# Lock-In_D2.net
KiCad netlist of a schematic drawn in EAGLE
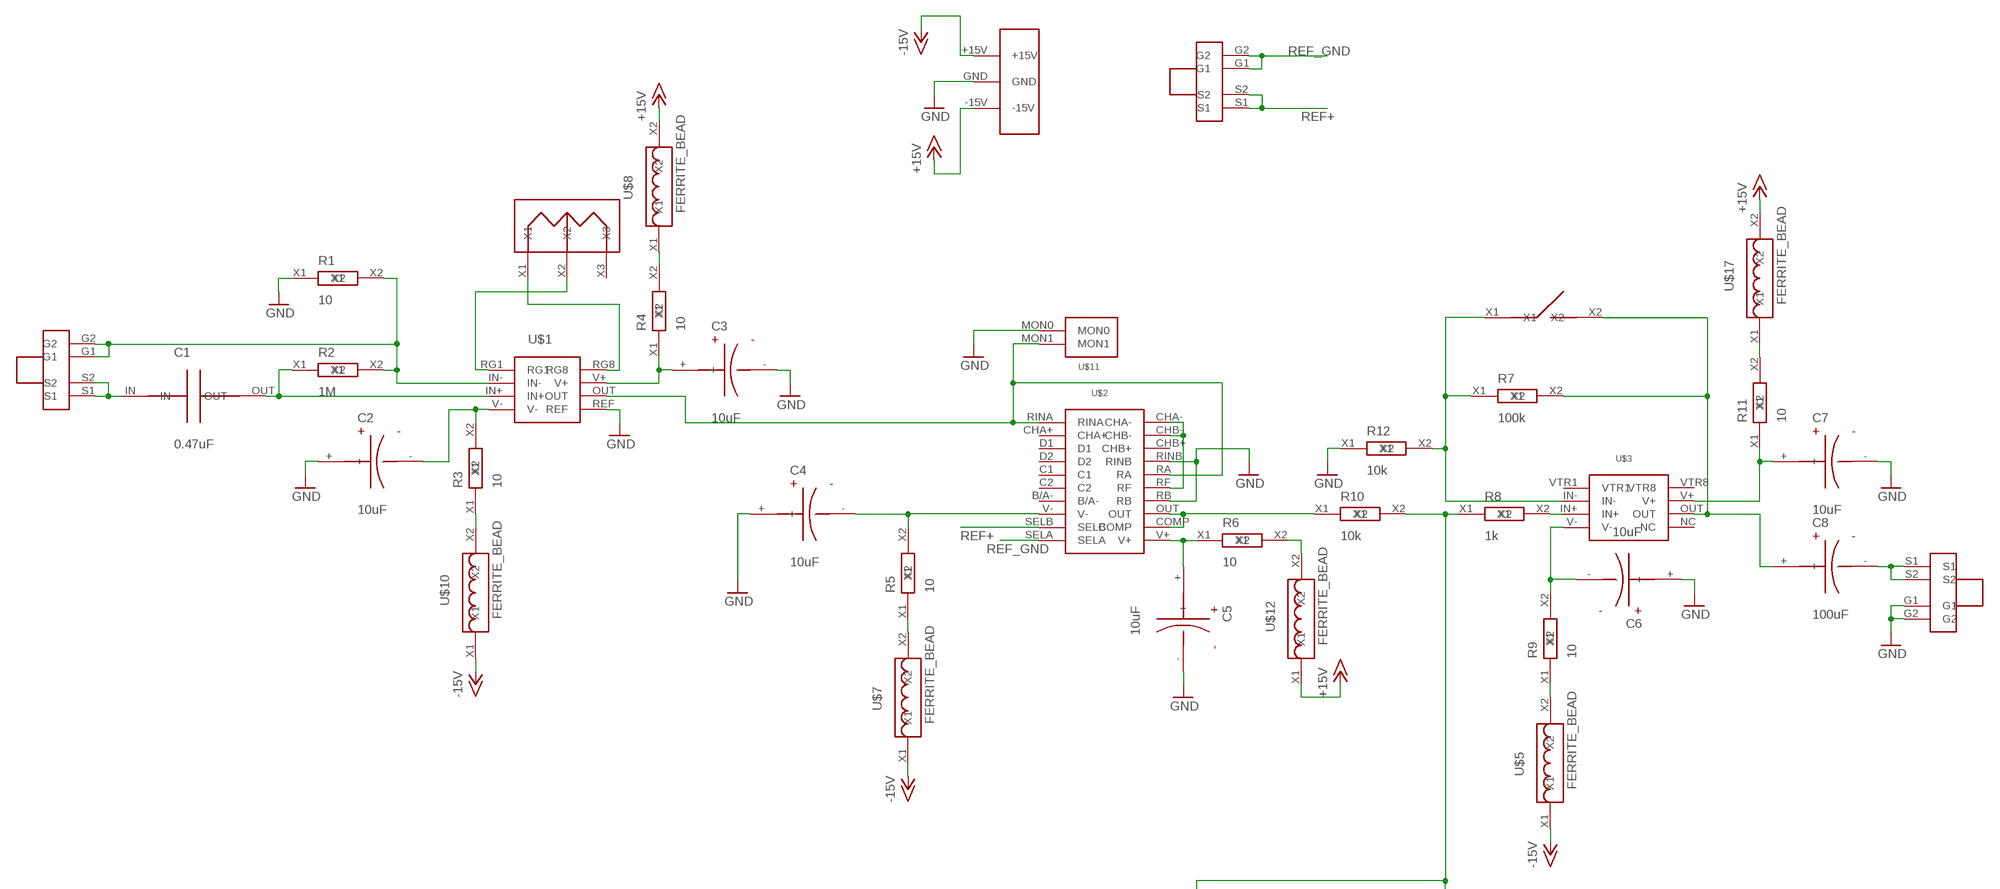
[diagram p0: schematic, sheet 1, part 1 of 2]
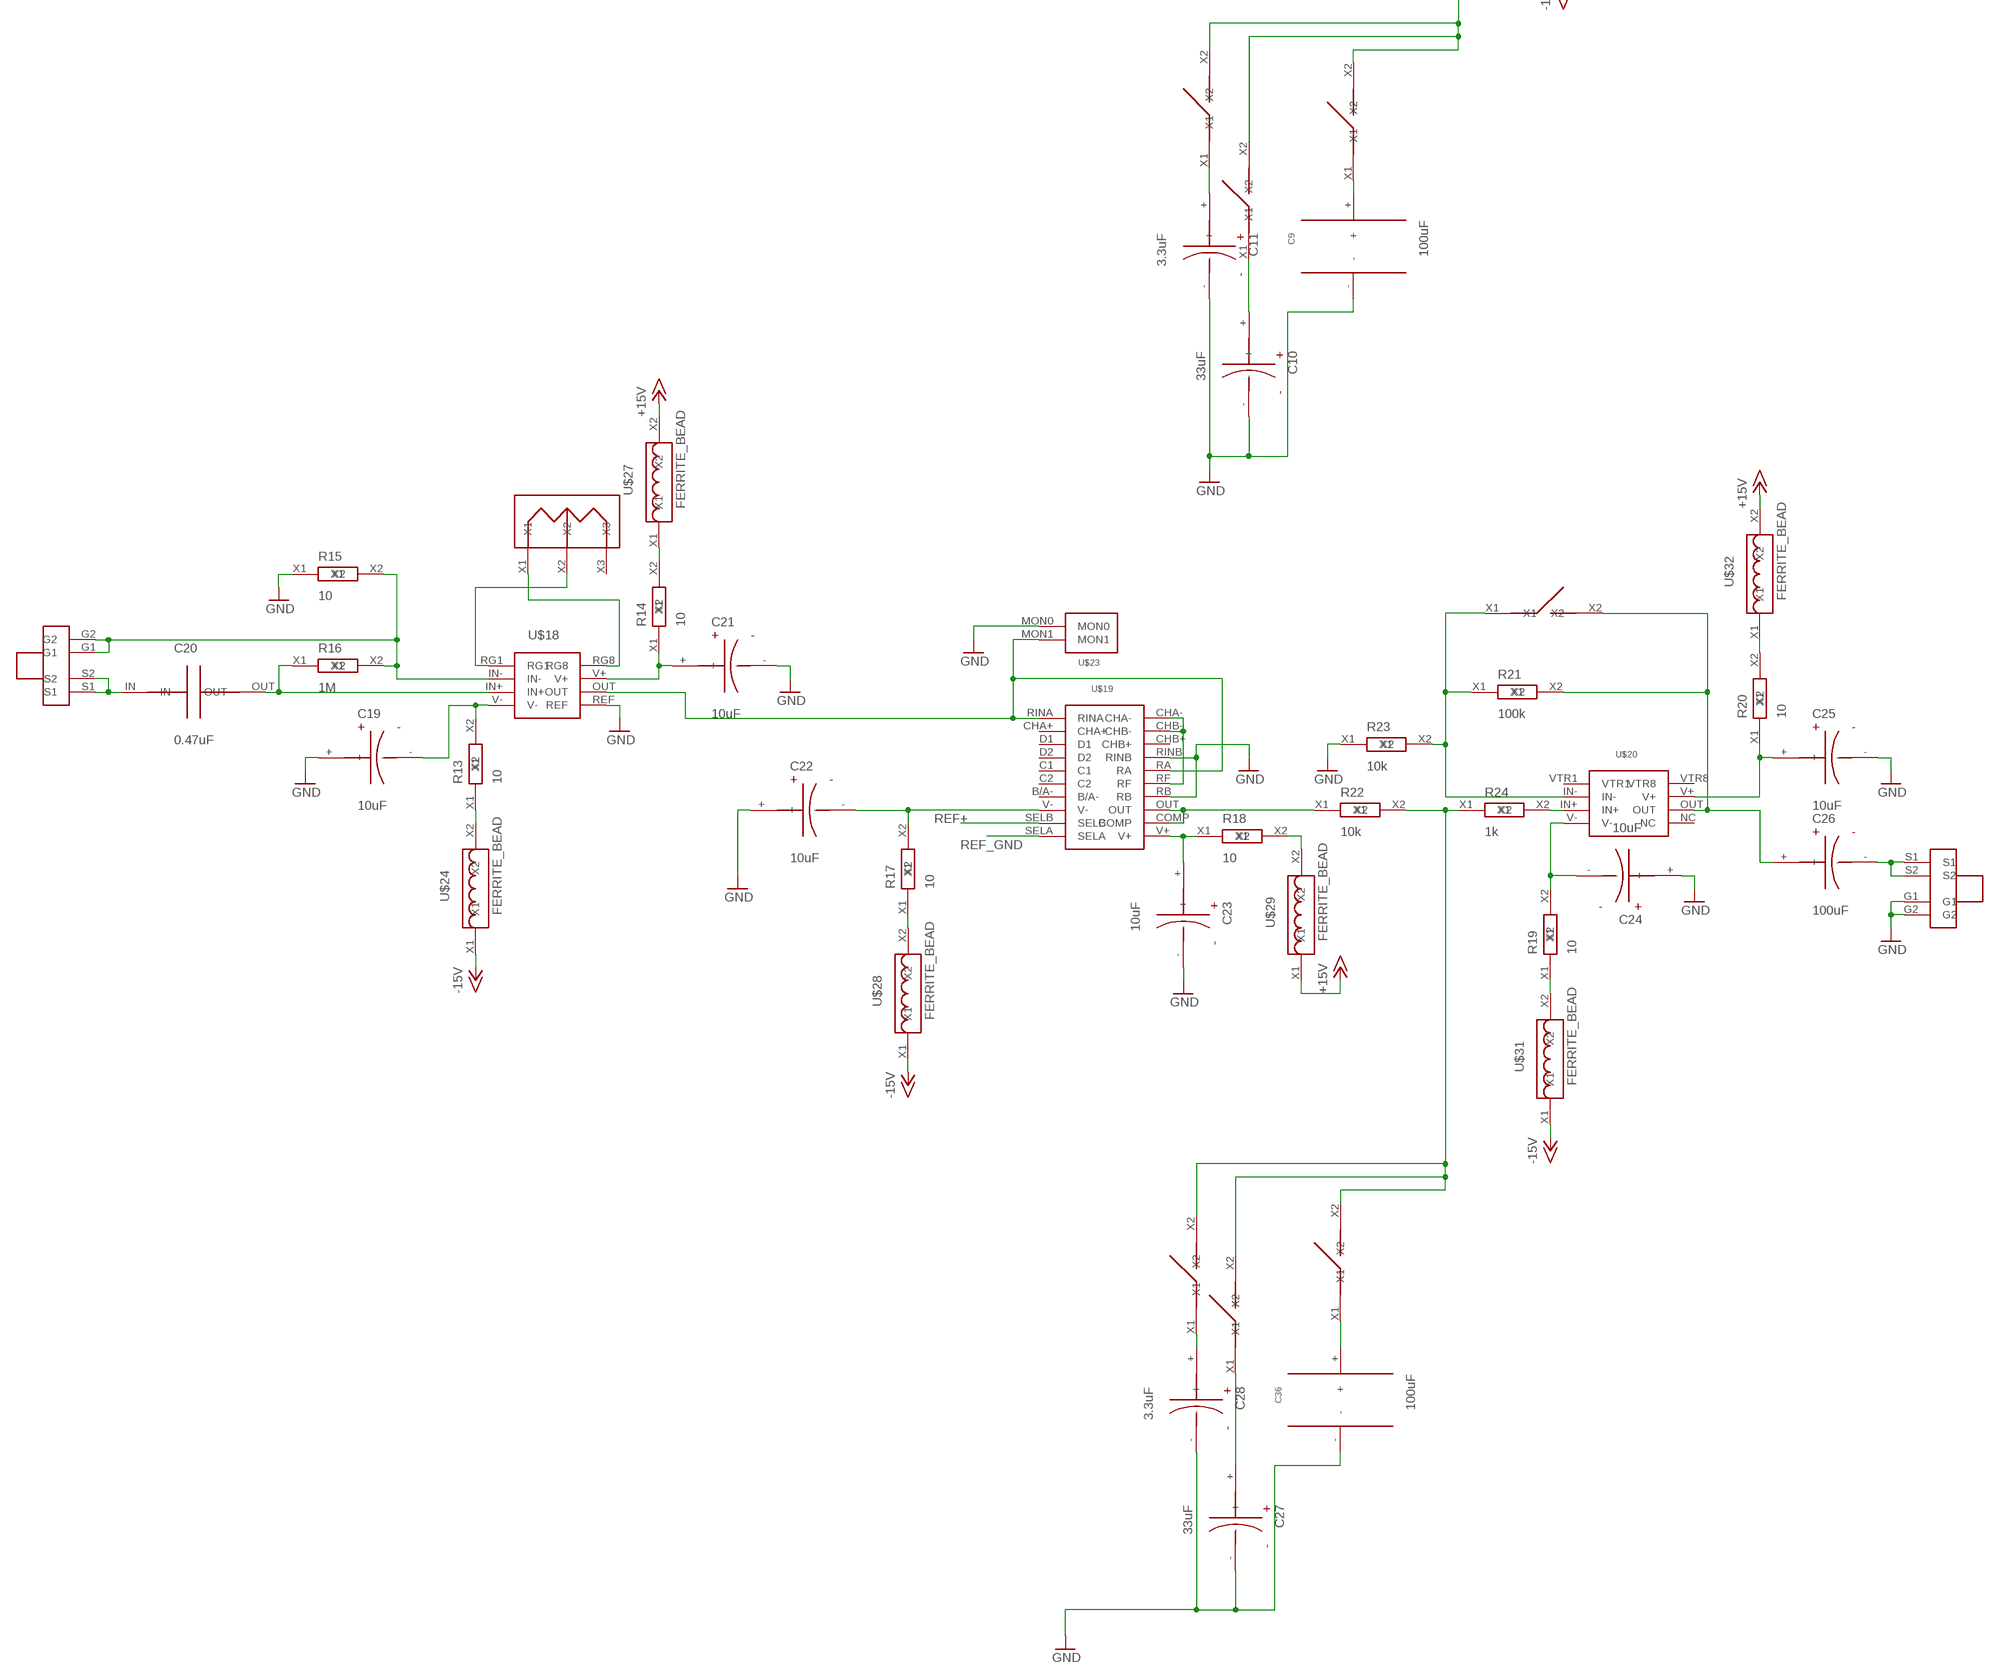
[diagram p1: schematic, sheet 1, part 2 of 2]

(export (version "E")
  (design (tool "Eeschema 10.0.6"))
  (components
    (comp (ref "C1")
      (value "0.47uF")
      (footprint "eagle-import:C_CER_5MM")
      (libsource (lib "eagle-import") (part "C_CER_5MM"))
    )
    (comp (ref "C2")
      (value "10uF")
      (footprint "eagle-import:C_ELT_2MM")
      (libsource (lib "eagle-import") (part "C_ELT_2MM"))
    )
    (comp (ref "C3")
      (value "10uF")
      (footprint "eagle-import:C_ELT_2MM")
      (libsource (lib "eagle-import") (part "C_ELT_2MM"))
    )
    (comp (ref "C4")
      (value "10uF")
      (footprint "eagle-import:C_ELT_2MM")
      (libsource (lib "eagle-import") (part "C_ELT_2MM"))
    )
    (comp (ref "C5")
      (value "10uF")
      (footprint "eagle-import:C_ELT_2MM")
      (libsource (lib "eagle-import") (part "C_ELT_2MM"))
    )
    (comp (ref "C6")
      (value "10uF")
      (footprint "eagle-import:C_ELT_2MM")
      (libsource (lib "eagle-import") (part "C_ELT_2MM"))
    )
    (comp (ref "C7")
      (value "10uF")
      (footprint "eagle-import:C_ELT_2MM")
      (libsource (lib "eagle-import") (part "C_ELT_2MM"))
    )
    (comp (ref "C8")
      (value "100uF")
      (footprint "eagle-import:C_ELT_2MM")
      (libsource (lib "eagle-import") (part "C_ELT_2MM"))
    )
    (comp (ref "C9")
      (value "100uF")
      (footprint "eagle-import:C100UF")
      (libsource (lib "eagle-import") (part "C100UF"))
    )
    (comp (ref "C10")
      (value "33uF")
      (footprint "eagle-import:C_ELT_2MM")
      (libsource (lib "eagle-import") (part "C_ELT_2MM"))
    )
    (comp (ref "C11")
      (value "3.3uF")
      (footprint "eagle-import:C_ELT_2MM")
      (libsource (lib "eagle-import") (part "C_ELT_2MM"))
    )
    (comp (ref "C19")
      (value "10uF")
      (footprint "eagle-import:C_ELT_2MM")
      (libsource (lib "eagle-import") (part "C_ELT_2MM"))
    )
    (comp (ref "C20")
      (value "0.47uF")
      (footprint "eagle-import:C_CER_5MM")
      (libsource (lib "eagle-import") (part "C_CER_5MM"))
    )
    (comp (ref "C21")
      (value "10uF")
      (footprint "eagle-import:C_ELT_2MM")
      (libsource (lib "eagle-import") (part "C_ELT_2MM"))
    )
    (comp (ref "C22")
      (value "10uF")
      (footprint "eagle-import:C_ELT_2MM")
      (libsource (lib "eagle-import") (part "C_ELT_2MM"))
    )
    (comp (ref "C23")
      (value "10uF")
      (footprint "eagle-import:C_ELT_2MM")
      (libsource (lib "eagle-import") (part "C_ELT_2MM"))
    )
    (comp (ref "C24")
      (value "10uF")
      (footprint "eagle-import:C_ELT_2MM")
      (libsource (lib "eagle-import") (part "C_ELT_2MM"))
    )
    (comp (ref "C25")
      (value "10uF")
      (footprint "eagle-import:C_ELT_2MM")
      (libsource (lib "eagle-import") (part "C_ELT_2MM"))
    )
    (comp (ref "C26")
      (value "100uF")
      (footprint "eagle-import:C_ELT_2MM")
      (libsource (lib "eagle-import") (part "C_ELT_2MM"))
    )
    (comp (ref "C27")
      (value "33uF")
      (footprint "eagle-import:C_ELT_2MM")
      (libsource (lib "eagle-import") (part "C_ELT_2MM"))
    )
    (comp (ref "C28")
      (value "3.3uF")
      (footprint "eagle-import:C_ELT_2MM")
      (libsource (lib "eagle-import") (part "C_ELT_2MM"))
    )
    (comp (ref "C36")
      (value "100uF")
      (footprint "eagle-import:C100UF")
      (libsource (lib "eagle-import") (part "C100UF"))
    )
    (comp (ref "R1")
      (value "10")
      (footprint "eagle-import:SMD_2.1X1.25")
      (libsource (lib "eagle-import") (part "R_SMD_2.1X1.25"))
    )
    (comp (ref "R2")
      (value "1M")
      (footprint "eagle-import:SMD_2.1X1.25")
      (libsource (lib "eagle-import") (part "R_SMD_2.1X1.25"))
    )
    (comp (ref "R3")
      (value "10")
      (footprint "eagle-import:SMD_2.1X1.25")
      (libsource (lib "eagle-import") (part "R_SMD_2.1X1.25"))
    )
    (comp (ref "R4")
      (value "10")
      (footprint "eagle-import:SMD_2.1X1.25")
      (libsource (lib "eagle-import") (part "R_SMD_2.1X1.25"))
    )
    (comp (ref "R5")
      (value "10")
      (footprint "eagle-import:SMD_2.1X1.25")
      (libsource (lib "eagle-import") (part "R_SMD_2.1X1.25"))
    )
    (comp (ref "R6")
      (value "10")
      (footprint "eagle-import:SMD_2.1X1.25")
      (libsource (lib "eagle-import") (part "R_SMD_2.1X1.25"))
    )
    (comp (ref "R7")
      (value "100k")
      (footprint "eagle-import:SMD_2.1X1.25")
      (libsource (lib "eagle-import") (part "R_SMD_2.1X1.25"))
    )
    (comp (ref "R8")
      (value "1k")
      (footprint "eagle-import:SMD_2.1X1.25")
      (libsource (lib "eagle-import") (part "R_SMD_2.1X1.25"))
    )
    (comp (ref "R9")
      (value "10")
      (footprint "eagle-import:SMD_2.1X1.25")
      (libsource (lib "eagle-import") (part "R_SMD_2.1X1.25"))
    )
    (comp (ref "R10")
      (value "10k")
      (footprint "eagle-import:SMD_2.1X1.25")
      (libsource (lib "eagle-import") (part "R_SMD_2.1X1.25"))
    )
    (comp (ref "R11")
      (value "10")
      (footprint "eagle-import:SMD_2.1X1.25")
      (libsource (lib "eagle-import") (part "R_SMD_2.1X1.25"))
    )
    (comp (ref "R12")
      (value "10k")
      (footprint "eagle-import:SMD_2.1X1.25")
      (libsource (lib "eagle-import") (part "R_SMD_2.1X1.25"))
    )
    (comp (ref "R13")
      (value "10")
      (footprint "eagle-import:SMD_2.1X1.25")
      (libsource (lib "eagle-import") (part "R_SMD_2.1X1.25"))
    )
    (comp (ref "R14")
      (value "10")
      (footprint "eagle-import:SMD_2.1X1.25")
      (libsource (lib "eagle-import") (part "R_SMD_2.1X1.25"))
    )
    (comp (ref "R15")
      (value "10")
      (footprint "eagle-import:SMD_2.1X1.25")
      (libsource (lib "eagle-import") (part "R_SMD_2.1X1.25"))
    )
    (comp (ref "R16")
      (value "1M")
      (footprint "eagle-import:SMD_2.1X1.25")
      (libsource (lib "eagle-import") (part "R_SMD_2.1X1.25"))
    )
    (comp (ref "R17")
      (value "10")
      (footprint "eagle-import:SMD_2.1X1.25")
      (libsource (lib "eagle-import") (part "R_SMD_2.1X1.25"))
    )
    (comp (ref "R18")
      (value "10")
      (footprint "eagle-import:SMD_2.1X1.25")
      (libsource (lib "eagle-import") (part "R_SMD_2.1X1.25"))
    )
    (comp (ref "R19")
      (value "10")
      (footprint "eagle-import:SMD_2.1X1.25")
      (libsource (lib "eagle-import") (part "R_SMD_2.1X1.25"))
    )
    (comp (ref "R20")
      (value "10")
      (footprint "eagle-import:SMD_2.1X1.25")
      (libsource (lib "eagle-import") (part "R_SMD_2.1X1.25"))
    )
    (comp (ref "R21")
      (value "100k")
      (footprint "eagle-import:SMD_2.1X1.25")
      (libsource (lib "eagle-import") (part "R_SMD_2.1X1.25"))
    )
    (comp (ref "R22")
      (value "10k")
      (footprint "eagle-import:SMD_2.1X1.25")
      (libsource (lib "eagle-import") (part "R_SMD_2.1X1.25"))
    )
    (comp (ref "R23")
      (value "10k")
      (footprint "eagle-import:SMD_2.1X1.25")
      (libsource (lib "eagle-import") (part "R_SMD_2.1X1.25"))
    )
    (comp (ref "R24")
      (value "1k")
      (footprint "eagle-import:SMD_2.1X1.25")
      (libsource (lib "eagle-import") (part "R_SMD_2.1X1.25"))
    )
    (comp (ref "U$1")
      (value "AD620N")
      (footprint "eagle-import:AD620N")
      (libsource (lib "eagle-import") (part "AD620N"))
    )
    (comp (ref "U$2")
      (value "AD630")
      (footprint "eagle-import:AD630")
      (libsource (lib "eagle-import") (part "AD630"))
    )
    (comp (ref "U$3")
      (value "OP27")
      (footprint "eagle-import:OP27")
      (libsource (lib "eagle-import") (part "OP27"))
    )
    (comp (ref "U$4")
      (value "BNC_A")
      (footprint "eagle-import:BNC_A")
      (libsource (lib "eagle-import") (part "BNC_A"))
    )
    (comp (ref "U$5")
      (value "FERRITE_BEAD")
      (footprint "eagle-import:FERRITE_BEAD")
      (libsource (lib "eagle-import") (part "FERRITE_BEAD"))
    )
    (comp (ref "U$6")
      (value "DIP_1")
      (footprint "eagle-import:DIP_1")
      (libsource (lib "eagle-import") (part "DIP_1"))
    )
    (comp (ref "U$7")
      (value "FERRITE_BEAD")
      (footprint "eagle-import:FERRITE_BEAD")
      (libsource (lib "eagle-import") (part "FERRITE_BEAD"))
    )
    (comp (ref "U$8")
      (value "FERRITE_BEAD")
      (footprint "eagle-import:FERRITE_BEAD")
      (libsource (lib "eagle-import") (part "FERRITE_BEAD"))
    )
    (comp (ref "U$9")
      (value "DIP_1")
      (footprint "eagle-import:DIP_1")
      (libsource (lib "eagle-import") (part "DIP_1"))
    )
    (comp (ref "U$10")
      (value "FERRITE_BEAD")
      (footprint "eagle-import:FERRITE_BEAD")
      (libsource (lib "eagle-import") (part "FERRITE_BEAD"))
    )
    (comp (ref "U$11")
      (value "MON2PIN")
      (footprint "eagle-import:MON2PIN")
      (libsource (lib "eagle-import") (part "MON2PIN"))
    )
    (comp (ref "U$12")
      (value "FERRITE_BEAD")
      (footprint "eagle-import:FERRITE_BEAD")
      (libsource (lib "eagle-import") (part "FERRITE_BEAD"))
    )
    (comp (ref "U$13")
      (value "BNC_A")
      (footprint "eagle-import:BNC_A")
      (libsource (lib "eagle-import") (part "BNC_A"))
    )
    (comp (ref "U$14")
      (value "R_VAR_3296W-1-103LF")
      (footprint "eagle-import:R_VAR_3296W-1-103LF")
      (libsource (lib "eagle-import") (part "R_VAR_3296W-1-103LF"))
    )
    (comp (ref "U$15")
      (value "SUPPLY")
      (footprint "eagle-import:SUPPLY")
      (libsource (lib "eagle-import") (part "SUPPLY"))
    )
    (comp (ref "U$16")
      (value "BNC_A")
      (footprint "eagle-import:BNC_A")
      (libsource (lib "eagle-import") (part "BNC_A"))
    )
    (comp (ref "U$17")
      (value "FERRITE_BEAD")
      (footprint "eagle-import:FERRITE_BEAD")
      (libsource (lib "eagle-import") (part "FERRITE_BEAD"))
    )
    (comp (ref "U$18")
      (value "AD620N")
      (footprint "eagle-import:AD620N")
      (libsource (lib "eagle-import") (part "AD620N"))
    )
    (comp (ref "U$19")
      (value "AD630")
      (footprint "eagle-import:AD630")
      (libsource (lib "eagle-import") (part "AD630"))
    )
    (comp (ref "U$20")
      (value "OP27")
      (footprint "eagle-import:OP27")
      (libsource (lib "eagle-import") (part "OP27"))
    )
    (comp (ref "U$21")
      (value "DIP_1")
      (footprint "eagle-import:DIP_1")
      (libsource (lib "eagle-import") (part "DIP_1"))
    )
    (comp (ref "U$22")
      (value "DIP_1")
      (footprint "eagle-import:DIP_1")
      (libsource (lib "eagle-import") (part "DIP_1"))
    )
    (comp (ref "U$23")
      (value "MON2PIN")
      (footprint "eagle-import:MON2PIN")
      (libsource (lib "eagle-import") (part "MON2PIN"))
    )
    (comp (ref "U$24")
      (value "FERRITE_BEAD")
      (footprint "eagle-import:FERRITE_BEAD")
      (libsource (lib "eagle-import") (part "FERRITE_BEAD"))
    )
    (comp (ref "U$25")
      (value "R_VAR_3296W-1-103LF")
      (footprint "eagle-import:R_VAR_3296W-1-103LF")
      (libsource (lib "eagle-import") (part "R_VAR_3296W-1-103LF"))
    )
    (comp (ref "U$26")
      (value "BNC_A")
      (footprint "eagle-import:BNC_A")
      (libsource (lib "eagle-import") (part "BNC_A"))
    )
    (comp (ref "U$27")
      (value "FERRITE_BEAD")
      (footprint "eagle-import:FERRITE_BEAD")
      (libsource (lib "eagle-import") (part "FERRITE_BEAD"))
    )
    (comp (ref "U$28")
      (value "FERRITE_BEAD")
      (footprint "eagle-import:FERRITE_BEAD")
      (libsource (lib "eagle-import") (part "FERRITE_BEAD"))
    )
    (comp (ref "U$29")
      (value "FERRITE_BEAD")
      (footprint "eagle-import:FERRITE_BEAD")
      (libsource (lib "eagle-import") (part "FERRITE_BEAD"))
    )
    (comp (ref "U$30")
      (value "BNC_A")
      (footprint "eagle-import:BNC_A")
      (libsource (lib "eagle-import") (part "BNC_A"))
    )
    (comp (ref "U$31")
      (value "FERRITE_BEAD")
      (footprint "eagle-import:FERRITE_BEAD")
      (libsource (lib "eagle-import") (part "FERRITE_BEAD"))
    )
    (comp (ref "U$32")
      (value "FERRITE_BEAD")
      (footprint "eagle-import:FERRITE_BEAD")
      (libsource (lib "eagle-import") (part "FERRITE_BEAD"))
    )
    (comp (ref "U$33")
      (value "DIP_1")
      (footprint "eagle-import:DIP_1")
      (libsource (lib "eagle-import") (part "DIP_1"))
    )
    (comp (ref "U$34")
      (value "DIP_1")
      (footprint "eagle-import:DIP_1")
      (libsource (lib "eagle-import") (part "DIP_1"))
    )
    (comp (ref "U$35")
      (value "DIP_1")
      (footprint "eagle-import:DIP_1")
      (libsource (lib "eagle-import") (part "DIP_1"))
    )
    (comp (ref "U$36")
      (value "DIP_1")
      (footprint "eagle-import:DIP_1")
      (libsource (lib "eagle-import") (part "DIP_1"))
    )
  )
  (nets
    (net (code "1") (name "+15V") (class "Default")
      (node (ref "U$12") (pin "X1") (pinfunction "X1_X1") (pintype "bidirectional"))
      (node (ref "U$15") (pin "-15V") (pinfunction "-15V_-15V") (pintype "bidirectional"))
      (node (ref "U$17") (pin "X2") (pinfunction "X2_X2") (pintype "bidirectional"))
      (node (ref "U$27") (pin "X2") (pinfunction "X2_X2") (pintype "bidirectional"))
      (node (ref "U$29") (pin "X1") (pinfunction "X1_X1") (pintype "bidirectional"))
      (node (ref "U$32") (pin "X2") (pinfunction "X2_X2") (pintype "bidirectional"))
      (node (ref "U$8") (pin "X2") (pinfunction "X2_X2") (pintype "bidirectional"))
    )
    (net (code "2") (name "-15V") (class "Default")
      (node (ref "U$10") (pin "X1") (pinfunction "X1_X1") (pintype "bidirectional"))
      (node (ref "U$15") (pin "+15V") (pinfunction "+15V_+15V") (pintype "bidirectional"))
      (node (ref "U$24") (pin "X1") (pinfunction "X1_X1") (pintype "bidirectional"))
      (node (ref "U$28") (pin "X1") (pinfunction "X1_X1") (pintype "bidirectional"))
      (node (ref "U$31") (pin "X1") (pinfunction "X1_X1") (pintype "bidirectional"))
      (node (ref "U$5") (pin "X1") (pinfunction "X1_X1") (pintype "bidirectional"))
      (node (ref "U$7") (pin "X1") (pinfunction "X1_X1") (pintype "bidirectional"))
    )
    (net (code "3") (name "/REF+") (class "Default")
      (node (ref "U$13") (pin "S1") (pinfunction "S1_S1") (pintype "bidirectional"))
      (node (ref "U$13") (pin "S2") (pinfunction "S2_S2") (pintype "bidirectional"))
      (node (ref "U$19") (pin "SELB") (pinfunction "SELB_SELB") (pintype "bidirectional"))
      (node (ref "U$2") (pin "SELB") (pinfunction "SELB_SELB") (pintype "bidirectional"))
    )
    (net (code "4") (name "/REF_GND") (class "Default")
      (node (ref "U$13") (pin "G1") (pinfunction "G1_G1") (pintype "bidirectional"))
      (node (ref "U$13") (pin "G2") (pinfunction "G2_G2") (pintype "bidirectional"))
      (node (ref "U$19") (pin "SELA") (pinfunction "SELA_SELA") (pintype "bidirectional"))
      (node (ref "U$2") (pin "SELA") (pinfunction "SELA_SELA") (pintype "bidirectional"))
    )
    (net (code "5") (name "GND") (class "Default")
      (node (ref "C10") (pin "-") (pinfunction "-_-") (pintype "bidirectional"))
      (node (ref "C11") (pin "-") (pinfunction "-_-") (pintype "bidirectional"))
      (node (ref "C19") (pin "+") (pinfunction "+_+") (pintype "bidirectional"))
      (node (ref "C2") (pin "+") (pinfunction "+_+") (pintype "bidirectional"))
      (node (ref "C21") (pin "-") (pinfunction "-_-") (pintype "bidirectional"))
      (node (ref "C22") (pin "+") (pinfunction "+_+") (pintype "bidirectional"))
      (node (ref "C23") (pin "-") (pinfunction "-_-") (pintype "bidirectional"))
      (node (ref "C24") (pin "+") (pinfunction "+_+") (pintype "bidirectional"))
      (node (ref "C25") (pin "-") (pinfunction "-_-") (pintype "bidirectional"))
      (node (ref "C27") (pin "-") (pinfunction "-_-") (pintype "bidirectional"))
      (node (ref "C28") (pin "-") (pinfunction "-_-") (pintype "bidirectional"))
      (node (ref "C3") (pin "-") (pinfunction "-_-") (pintype "bidirectional"))
      (node (ref "C36") (pin "-") (pinfunction "-_-") (pintype "bidirectional"))
      (node (ref "C4") (pin "+") (pinfunction "+_+") (pintype "bidirectional"))
      (node (ref "C5") (pin "-") (pinfunction "-_-") (pintype "bidirectional"))
      (node (ref "C6") (pin "+") (pinfunction "+_+") (pintype "bidirectional"))
      (node (ref "C7") (pin "-") (pinfunction "-_-") (pintype "bidirectional"))
      (node (ref "C9") (pin "-") (pinfunction "-_-") (pintype "bidirectional"))
      (node (ref "R1") (pin "X1") (pinfunction "X1_X1") (pintype "bidirectional"))
      (node (ref "R12") (pin "X1") (pinfunction "X1_X1") (pintype "bidirectional"))
      (node (ref "R15") (pin "X1") (pinfunction "X1_X1") (pintype "bidirectional"))
      (node (ref "R23") (pin "X1") (pinfunction "X1_X1") (pintype "bidirectional"))
      (node (ref "U$1") (pin "REF") (pinfunction "REF_REF") (pintype "bidirectional"))
      (node (ref "U$11") (pin "MON0") (pinfunction "MON0_MON0") (pintype "bidirectional"))
      (node (ref "U$15") (pin "GND") (pinfunction "GND_GND") (pintype "bidirectional"))
      (node (ref "U$18") (pin "REF") (pinfunction "REF_REF") (pintype "bidirectional"))
      (node (ref "U$19") (pin "RB") (pinfunction "RB_RB") (pintype "bidirectional"))
      (node (ref "U$19") (pin "RINB") (pinfunction "RINB_RINB") (pintype "bidirectional"))
      (node (ref "U$2") (pin "RB") (pinfunction "RB_RB") (pintype "bidirectional"))
      (node (ref "U$2") (pin "RINB") (pinfunction "RINB_RINB") (pintype "bidirectional"))
      (node (ref "U$23") (pin "MON0") (pinfunction "MON0_MON0") (pintype "bidirectional"))
      (node (ref "U$30") (pin "G1") (pinfunction "G1_G1") (pintype "bidirectional"))
      (node (ref "U$30") (pin "G2") (pinfunction "G2_G2") (pintype "bidirectional"))
      (node (ref "U$4") (pin "G1") (pinfunction "G1_G1") (pintype "bidirectional"))
      (node (ref "U$4") (pin "G2") (pinfunction "G2_G2") (pintype "bidirectional"))
    )
    (net (code "6") (name "Net-(C1-PadIN)") (class "Default")
      (node (ref "C1") (pin "IN") (pinfunction "IN_IN") (pintype "bidirectional"))
      (node (ref "U$16") (pin "S1") (pinfunction "S1_S1") (pintype "bidirectional"))
      (node (ref "U$16") (pin "S2") (pinfunction "S2_S2") (pintype "bidirectional"))
    )
    (net (code "7") (name "Net-(C1-PadOUT)") (class "Default")
      (node (ref "C1") (pin "OUT") (pinfunction "OUT_OUT") (pintype "bidirectional"))
      (node (ref "R2") (pin "X1") (pinfunction "X1_X1") (pintype "bidirectional"))
      (node (ref "U$1") (pin "IN+") (pinfunction "IN+_IN+") (pintype "bidirectional"))
    )
    (net (code "8") (name "Net-(C2-Pad-)") (class "Default")
      (node (ref "C2") (pin "-") (pinfunction "-_-") (pintype "bidirectional"))
      (node (ref "R3") (pin "X2") (pinfunction "X2_X2") (pintype "bidirectional"))
      (node (ref "U$1") (pin "V-") (pinfunction "V-_V-") (pintype "bidirectional"))
    )
    (net (code "9") (name "Net-(C3-Pad+)") (class "Default")
      (node (ref "C3") (pin "+") (pinfunction "+_+") (pintype "bidirectional"))
      (node (ref "R4") (pin "X1") (pinfunction "X1_X1") (pintype "bidirectional"))
      (node (ref "U$1") (pin "V+") (pinfunction "V+_V+") (pintype "bidirectional"))
    )
    (net (code "10") (name "Net-(C4-Pad-)") (class "Default")
      (node (ref "C4") (pin "-") (pinfunction "-_-") (pintype "bidirectional"))
      (node (ref "R5") (pin "X2") (pinfunction "X2_X2") (pintype "bidirectional"))
      (node (ref "U$2") (pin "V-") (pinfunction "V-_V-") (pintype "bidirectional"))
    )
    (net (code "11") (name "Net-(C5-Pad+)") (class "Default")
      (node (ref "C5") (pin "+") (pinfunction "+_+") (pintype "bidirectional"))
      (node (ref "R6") (pin "X1") (pinfunction "X1_X1") (pintype "bidirectional"))
      (node (ref "U$2") (pin "V+") (pinfunction "V+_V+") (pintype "bidirectional"))
    )
    (net (code "12") (name "Net-(C6-Pad-)") (class "Default")
      (node (ref "C6") (pin "-") (pinfunction "-_-") (pintype "bidirectional"))
      (node (ref "R9") (pin "X2") (pinfunction "X2_X2") (pintype "bidirectional"))
      (node (ref "U$3") (pin "V-") (pinfunction "V-_V-") (pintype "bidirectional"))
    )
    (net (code "13") (name "Net-(C7-Pad+)") (class "Default")
      (node (ref "C7") (pin "+") (pinfunction "+_+") (pintype "bidirectional"))
      (node (ref "R11") (pin "X1") (pinfunction "X1_X1") (pintype "bidirectional"))
      (node (ref "U$3") (pin "V+") (pinfunction "V+_V+") (pintype "bidirectional"))
    )
    (net (code "14") (name "Net-(C8-Pad+)") (class "Default")
      (node (ref "C8") (pin "+") (pinfunction "+_+") (pintype "bidirectional"))
      (node (ref "R7") (pin "X2") (pinfunction "X2_X2") (pintype "bidirectional"))
      (node (ref "U$3") (pin "OUT") (pinfunction "OUT_OUT") (pintype "bidirectional"))
      (node (ref "U$9") (pin "X2") (pinfunction "X2_X2") (pintype "bidirectional"))
    )
    (net (code "15") (name "Net-(C8-Pad-)") (class "Default")
      (node (ref "C8") (pin "-") (pinfunction "-_-") (pintype "bidirectional"))
      (node (ref "U$4") (pin "S1") (pinfunction "S1_S1") (pintype "bidirectional"))
      (node (ref "U$4") (pin "S2") (pinfunction "S2_S2") (pintype "bidirectional"))
    )
    (net (code "16") (name "Net-(C9-Pad+)") (class "Default")
      (node (ref "C9") (pin "+") (pinfunction "+_+") (pintype "bidirectional"))
      (node (ref "U$36") (pin "X1") (pinfunction "X1_X1") (pintype "bidirectional"))
    )
    (net (code "17") (name "Net-(C10-Pad+)") (class "Default")
      (node (ref "C10") (pin "+") (pinfunction "+_+") (pintype "bidirectional"))
      (node (ref "U$35") (pin "X1") (pinfunction "X1_X1") (pintype "bidirectional"))
    )
    (net (code "18") (name "Net-(C11-Pad+)") (class "Default")
      (node (ref "C11") (pin "+") (pinfunction "+_+") (pintype "bidirectional"))
      (node (ref "U$34") (pin "X1") (pinfunction "X1_X1") (pintype "bidirectional"))
    )
    (net (code "19") (name "Net-(C19-Pad-)") (class "Default")
      (node (ref "C19") (pin "-") (pinfunction "-_-") (pintype "bidirectional"))
      (node (ref "R13") (pin "X2") (pinfunction "X2_X2") (pintype "bidirectional"))
      (node (ref "U$18") (pin "V-") (pinfunction "V-_V-") (pintype "bidirectional"))
    )
    (net (code "20") (name "Net-(C20-PadIN)") (class "Default")
      (node (ref "C20") (pin "IN") (pinfunction "IN_IN") (pintype "bidirectional"))
      (node (ref "U$26") (pin "S1") (pinfunction "S1_S1") (pintype "bidirectional"))
      (node (ref "U$26") (pin "S2") (pinfunction "S2_S2") (pintype "bidirectional"))
    )
    (net (code "21") (name "Net-(C20-PadOUT)") (class "Default")
      (node (ref "C20") (pin "OUT") (pinfunction "OUT_OUT") (pintype "bidirectional"))
      (node (ref "R16") (pin "X1") (pinfunction "X1_X1") (pintype "bidirectional"))
      (node (ref "U$18") (pin "IN+") (pinfunction "IN+_IN+") (pintype "bidirectional"))
    )
    (net (code "22") (name "Net-(C21-Pad+)") (class "Default")
      (node (ref "C21") (pin "+") (pinfunction "+_+") (pintype "bidirectional"))
      (node (ref "R14") (pin "X1") (pinfunction "X1_X1") (pintype "bidirectional"))
      (node (ref "U$18") (pin "V+") (pinfunction "V+_V+") (pintype "bidirectional"))
    )
    (net (code "23") (name "Net-(C22-Pad-)") (class "Default")
      (node (ref "C22") (pin "-") (pinfunction "-_-") (pintype "bidirectional"))
      (node (ref "R17") (pin "X2") (pinfunction "X2_X2") (pintype "bidirectional"))
      (node (ref "U$19") (pin "V-") (pinfunction "V-_V-") (pintype "bidirectional"))
    )
    (net (code "24") (name "Net-(C23-Pad+)") (class "Default")
      (node (ref "C23") (pin "+") (pinfunction "+_+") (pintype "bidirectional"))
      (node (ref "R18") (pin "X1") (pinfunction "X1_X1") (pintype "bidirectional"))
      (node (ref "U$19") (pin "V+") (pinfunction "V+_V+") (pintype "bidirectional"))
    )
    (net (code "25") (name "Net-(C24-Pad-)") (class "Default")
      (node (ref "C24") (pin "-") (pinfunction "-_-") (pintype "bidirectional"))
      (node (ref "R19") (pin "X2") (pinfunction "X2_X2") (pintype "bidirectional"))
      (node (ref "U$20") (pin "V-") (pinfunction "V-_V-") (pintype "bidirectional"))
    )
    (net (code "26") (name "Net-(C25-Pad+)") (class "Default")
      (node (ref "C25") (pin "+") (pinfunction "+_+") (pintype "bidirectional"))
      (node (ref "R20") (pin "X1") (pinfunction "X1_X1") (pintype "bidirectional"))
      (node (ref "U$20") (pin "V+") (pinfunction "V+_V+") (pintype "bidirectional"))
    )
    (net (code "27") (name "Net-(C26-Pad+)") (class "Default")
      (node (ref "C26") (pin "+") (pinfunction "+_+") (pintype "bidirectional"))
      (node (ref "R21") (pin "X2") (pinfunction "X2_X2") (pintype "bidirectional"))
      (node (ref "U$20") (pin "OUT") (pinfunction "OUT_OUT") (pintype "bidirectional"))
      (node (ref "U$22") (pin "X2") (pinfunction "X2_X2") (pintype "bidirectional"))
    )
    (net (code "28") (name "Net-(C26-Pad-)") (class "Default")
      (node (ref "C26") (pin "-") (pinfunction "-_-") (pintype "bidirectional"))
      (node (ref "U$30") (pin "S1") (pinfunction "S1_S1") (pintype "bidirectional"))
      (node (ref "U$30") (pin "S2") (pinfunction "S2_S2") (pintype "bidirectional"))
    )
    (net (code "29") (name "Net-(C27-Pad+)") (class "Default")
      (node (ref "C27") (pin "+") (pinfunction "+_+") (pintype "bidirectional"))
      (node (ref "U$33") (pin "X1") (pinfunction "X1_X1") (pintype "bidirectional"))
    )
    (net (code "30") (name "Net-(C28-Pad+)") (class "Default")
      (node (ref "C28") (pin "+") (pinfunction "+_+") (pintype "bidirectional"))
      (node (ref "U$21") (pin "X1") (pinfunction "X1_X1") (pintype "bidirectional"))
    )
    (net (code "31") (name "Net-(C36-Pad+)") (class "Default")
      (node (ref "C36") (pin "+") (pinfunction "+_+") (pintype "bidirectional"))
      (node (ref "U$6") (pin "X1") (pinfunction "X1_X1") (pintype "bidirectional"))
    )
    (net (code "32") (name "Net-(R1-PadX2)") (class "Default")
      (node (ref "R1") (pin "X2") (pinfunction "X2_X2") (pintype "bidirectional"))
      (node (ref "R2") (pin "X2") (pinfunction "X2_X2") (pintype "bidirectional"))
      (node (ref "U$1") (pin "IN-") (pinfunction "IN-_IN-") (pintype "bidirectional"))
      (node (ref "U$16") (pin "G1") (pinfunction "G1_G1") (pintype "bidirectional"))
      (node (ref "U$16") (pin "G2") (pinfunction "G2_G2") (pintype "bidirectional"))
    )
    (net (code "33") (name "Net-(R3-PadX1)") (class "Default")
      (node (ref "R3") (pin "X1") (pinfunction "X1_X1") (pintype "bidirectional"))
      (node (ref "U$10") (pin "X2") (pinfunction "X2_X2") (pintype "bidirectional"))
    )
    (net (code "34") (name "Net-(R4-PadX2)") (class "Default")
      (node (ref "R4") (pin "X2") (pinfunction "X2_X2") (pintype "bidirectional"))
      (node (ref "U$8") (pin "X1") (pinfunction "X1_X1") (pintype "bidirectional"))
    )
    (net (code "35") (name "Net-(R5-PadX1)") (class "Default")
      (node (ref "R5") (pin "X1") (pinfunction "X1_X1") (pintype "bidirectional"))
      (node (ref "U$7") (pin "X2") (pinfunction "X2_X2") (pintype "bidirectional"))
    )
    (net (code "36") (name "Net-(R6-PadX2)") (class "Default")
      (node (ref "R6") (pin "X2") (pinfunction "X2_X2") (pintype "bidirectional"))
      (node (ref "U$12") (pin "X2") (pinfunction "X2_X2") (pintype "bidirectional"))
    )
    (net (code "37") (name "Net-(R8-PadX2)") (class "Default")
      (node (ref "R8") (pin "X2") (pinfunction "X2_X2") (pintype "bidirectional"))
      (node (ref "U$3") (pin "IN+") (pinfunction "IN+_IN+") (pintype "bidirectional"))
    )
    (net (code "38") (name "Net-(R9-PadX1)") (class "Default")
      (node (ref "R9") (pin "X1") (pinfunction "X1_X1") (pintype "bidirectional"))
      (node (ref "U$5") (pin "X2") (pinfunction "X2_X2") (pintype "bidirectional"))
    )
    (net (code "39") (name "Net-(R10-PadX1)") (class "Default")
      (node (ref "R10") (pin "X1") (pinfunction "X1_X1") (pintype "bidirectional"))
      (node (ref "U$2") (pin "COMP") (pinfunction "COMP_COMP") (pintype "bidirectional"))
      (node (ref "U$2") (pin "OUT") (pinfunction "OUT_OUT") (pintype "bidirectional"))
    )
    (net (code "40") (name "Net-(R10-PadX2)") (class "Default")
      (node (ref "R10") (pin "X2") (pinfunction "X2_X2") (pintype "bidirectional"))
      (node (ref "R8") (pin "X1") (pinfunction "X1_X1") (pintype "bidirectional"))
      (node (ref "U$34") (pin "X2") (pinfunction "X2_X2") (pintype "bidirectional"))
      (node (ref "U$35") (pin "X2") (pinfunction "X2_X2") (pintype "bidirectional"))
      (node (ref "U$36") (pin "X2") (pinfunction "X2_X2") (pintype "bidirectional"))
    )
    (net (code "41") (name "Net-(R11-PadX2)") (class "Default")
      (node (ref "R11") (pin "X2") (pinfunction "X2_X2") (pintype "bidirectional"))
      (node (ref "U$17") (pin "X1") (pinfunction "X1_X1") (pintype "bidirectional"))
    )
    (net (code "42") (name "Net-(R12-PadX2)") (class "Default")
      (node (ref "R12") (pin "X2") (pinfunction "X2_X2") (pintype "bidirectional"))
      (node (ref "R7") (pin "X1") (pinfunction "X1_X1") (pintype "bidirectional"))
      (node (ref "U$3") (pin "IN-") (pinfunction "IN-_IN-") (pintype "bidirectional"))
      (node (ref "U$9") (pin "X1") (pinfunction "X1_X1") (pintype "bidirectional"))
    )
    (net (code "43") (name "Net-(R13-PadX1)") (class "Default")
      (node (ref "R13") (pin "X1") (pinfunction "X1_X1") (pintype "bidirectional"))
      (node (ref "U$24") (pin "X2") (pinfunction "X2_X2") (pintype "bidirectional"))
    )
    (net (code "44") (name "Net-(R14-PadX2)") (class "Default")
      (node (ref "R14") (pin "X2") (pinfunction "X2_X2") (pintype "bidirectional"))
      (node (ref "U$27") (pin "X1") (pinfunction "X1_X1") (pintype "bidirectional"))
    )
    (net (code "45") (name "Net-(R15-PadX2)") (class "Default")
      (node (ref "R15") (pin "X2") (pinfunction "X2_X2") (pintype "bidirectional"))
      (node (ref "R16") (pin "X2") (pinfunction "X2_X2") (pintype "bidirectional"))
      (node (ref "U$18") (pin "IN-") (pinfunction "IN-_IN-") (pintype "bidirectional"))
      (node (ref "U$26") (pin "G1") (pinfunction "G1_G1") (pintype "bidirectional"))
      (node (ref "U$26") (pin "G2") (pinfunction "G2_G2") (pintype "bidirectional"))
    )
    (net (code "46") (name "Net-(R17-PadX1)") (class "Default")
      (node (ref "R17") (pin "X1") (pinfunction "X1_X1") (pintype "bidirectional"))
      (node (ref "U$28") (pin "X2") (pinfunction "X2_X2") (pintype "bidirectional"))
    )
    (net (code "47") (name "Net-(R18-PadX2)") (class "Default")
      (node (ref "R18") (pin "X2") (pinfunction "X2_X2") (pintype "bidirectional"))
      (node (ref "U$29") (pin "X2") (pinfunction "X2_X2") (pintype "bidirectional"))
    )
    (net (code "48") (name "Net-(R19-PadX1)") (class "Default")
      (node (ref "R19") (pin "X1") (pinfunction "X1_X1") (pintype "bidirectional"))
      (node (ref "U$31") (pin "X2") (pinfunction "X2_X2") (pintype "bidirectional"))
    )
    (net (code "49") (name "Net-(R20-PadX2)") (class "Default")
      (node (ref "R20") (pin "X2") (pinfunction "X2_X2") (pintype "bidirectional"))
      (node (ref "U$32") (pin "X1") (pinfunction "X1_X1") (pintype "bidirectional"))
    )
    (net (code "50") (name "Net-(R21-PadX1)") (class "Default")
      (node (ref "R21") (pin "X1") (pinfunction "X1_X1") (pintype "bidirectional"))
      (node (ref "R23") (pin "X2") (pinfunction "X2_X2") (pintype "bidirectional"))
      (node (ref "U$20") (pin "IN-") (pinfunction "IN-_IN-") (pintype "bidirectional"))
      (node (ref "U$22") (pin "X1") (pinfunction "X1_X1") (pintype "bidirectional"))
    )
    (net (code "51") (name "Net-(R22-PadX1)") (class "Default")
      (node (ref "R22") (pin "X1") (pinfunction "X1_X1") (pintype "bidirectional"))
      (node (ref "U$19") (pin "COMP") (pinfunction "COMP_COMP") (pintype "bidirectional"))
      (node (ref "U$19") (pin "OUT") (pinfunction "OUT_OUT") (pintype "bidirectional"))
    )
    (net (code "52") (name "Net-(R22-PadX2)") (class "Default")
      (node (ref "R22") (pin "X2") (pinfunction "X2_X2") (pintype "bidirectional"))
      (node (ref "R24") (pin "X1") (pinfunction "X1_X1") (pintype "bidirectional"))
      (node (ref "U$21") (pin "X2") (pinfunction "X2_X2") (pintype "bidirectional"))
      (node (ref "U$33") (pin "X2") (pinfunction "X2_X2") (pintype "bidirectional"))
      (node (ref "U$6") (pin "X2") (pinfunction "X2_X2") (pintype "bidirectional"))
    )
    (net (code "53") (name "Net-(R24-PadX2)") (class "Default")
      (node (ref "R24") (pin "X2") (pinfunction "X2_X2") (pintype "bidirectional"))
      (node (ref "U$20") (pin "IN+") (pinfunction "IN+_IN+") (pintype "bidirectional"))
    )
    (net (code "54") (name "Net-(U$1-PadOUT)") (class "Default")
      (node (ref "U$1") (pin "OUT") (pinfunction "OUT_OUT") (pintype "bidirectional"))
      (node (ref "U$11") (pin "MON1") (pinfunction "MON1_MON1") (pintype "bidirectional"))
      (node (ref "U$2") (pin "RA") (pinfunction "RA_RA") (pintype "bidirectional"))
      (node (ref "U$2") (pin "RINA") (pinfunction "RINA_RINA") (pintype "bidirectional"))
    )
    (net (code "55") (name "Net-(U$1-PadRG1)") (class "Default")
      (node (ref "U$1") (pin "RG1") (pinfunction "RG1_RG1") (pintype "bidirectional"))
      (node (ref "U$14") (pin "X2") (pinfunction "X2_X2") (pintype "bidirectional"))
    )
    (net (code "56") (name "Net-(U$1-PadRG8)") (class "Default")
      (node (ref "U$1") (pin "RG8") (pinfunction "RG8_RG8") (pintype "bidirectional"))
      (node (ref "U$14") (pin "X1") (pinfunction "X1_X1") (pintype "bidirectional"))
    )
    (net (code "57") (name "Net-(U$2-PadCHA-)") (class "Default")
      (node (ref "U$2") (pin "CHA-") (pinfunction "CHA-_CHA-") (pintype "bidirectional"))
      (node (ref "U$2") (pin "CHB-") (pinfunction "CHB-_CHB-") (pintype "bidirectional"))
      (node (ref "U$2") (pin "RF") (pinfunction "RF_RF") (pintype "bidirectional"))
    )
    (net (code "58") (name "Net-(U$18-PadOUT)") (class "Default")
      (node (ref "U$18") (pin "OUT") (pinfunction "OUT_OUT") (pintype "bidirectional"))
      (node (ref "U$19") (pin "RA") (pinfunction "RA_RA") (pintype "bidirectional"))
      (node (ref "U$19") (pin "RINA") (pinfunction "RINA_RINA") (pintype "bidirectional"))
      (node (ref "U$23") (pin "MON1") (pinfunction "MON1_MON1") (pintype "bidirectional"))
    )
    (net (code "59") (name "Net-(U$18-PadRG1)") (class "Default")
      (node (ref "U$18") (pin "RG1") (pinfunction "RG1_RG1") (pintype "bidirectional"))
      (node (ref "U$25") (pin "X2") (pinfunction "X2_X2") (pintype "bidirectional"))
    )
    (net (code "60") (name "Net-(U$18-PadRG8)") (class "Default")
      (node (ref "U$18") (pin "RG8") (pinfunction "RG8_RG8") (pintype "bidirectional"))
      (node (ref "U$25") (pin "X1") (pinfunction "X1_X1") (pintype "bidirectional"))
    )
    (net (code "61") (name "Net-(U$19-PadCHA-)") (class "Default")
      (node (ref "U$19") (pin "CHA-") (pinfunction "CHA-_CHA-") (pintype "bidirectional"))
      (node (ref "U$19") (pin "CHB-") (pinfunction "CHB-_CHB-") (pintype "bidirectional"))
      (node (ref "U$19") (pin "RF") (pinfunction "RF_RF") (pintype "bidirectional"))
    )
    (net (code "62") (name "unconnected-(U$2-PadB{slash}A-)") (class "Default")
      (node (ref "U$2") (pin "B/A-") (pinfunction "B/A-_B/A-") (pintype "bidirectional"))
    )
    (net (code "63") (name "unconnected-(U$2-PadC1)") (class "Default")
      (node (ref "U$2") (pin "C1") (pinfunction "C1_C1") (pintype "bidirectional"))
    )
    (net (code "64") (name "unconnected-(U$2-PadC2)") (class "Default")
      (node (ref "U$2") (pin "C2") (pinfunction "C2_C2") (pintype "bidirectional"))
    )
    (net (code "65") (name "unconnected-(U$2-PadCHA+)") (class "Default")
      (node (ref "U$2") (pin "CHA+") (pinfunction "CHA+_CHA+") (pintype "bidirectional"))
    )
    (net (code "66") (name "unconnected-(U$2-PadCHB+)") (class "Default")
      (node (ref "U$2") (pin "CHB+") (pinfunction "CHB+_CHB+") (pintype "bidirectional"))
    )
    (net (code "67") (name "unconnected-(U$2-PadD1)") (class "Default")
      (node (ref "U$2") (pin "D1") (pinfunction "D1_D1") (pintype "bidirectional"))
    )
    (net (code "68") (name "unconnected-(U$2-PadD2)") (class "Default")
      (node (ref "U$2") (pin "D2") (pinfunction "D2_D2") (pintype "bidirectional"))
    )
    (net (code "69") (name "unconnected-(U$3-PadNC)") (class "Default")
      (node (ref "U$3") (pin "NC") (pinfunction "NC_NC") (pintype "bidirectional"))
    )
    (net (code "70") (name "unconnected-(U$3-PadVTR1)") (class "Default")
      (node (ref "U$3") (pin "VTR1") (pinfunction "VTR1_VTR1") (pintype "bidirectional"))
    )
    (net (code "71") (name "unconnected-(U$3-PadVTR8)") (class "Default")
      (node (ref "U$3") (pin "VTR8") (pinfunction "VTR8_VTR8") (pintype "bidirectional"))
    )
    (net (code "72") (name "unconnected-(U$14-PadX3)") (class "Default")
      (node (ref "U$14") (pin "X3") (pinfunction "X3_X3") (pintype "bidirectional"))
    )
    (net (code "73") (name "unconnected-(U$19-PadB{slash}A-)") (class "Default")
      (node (ref "U$19") (pin "B/A-") (pinfunction "B/A-_B/A-") (pintype "bidirectional"))
    )
    (net (code "74") (name "unconnected-(U$19-PadC1)") (class "Default")
      (node (ref "U$19") (pin "C1") (pinfunction "C1_C1") (pintype "bidirectional"))
    )
    (net (code "75") (name "unconnected-(U$19-PadC2)") (class "Default")
      (node (ref "U$19") (pin "C2") (pinfunction "C2_C2") (pintype "bidirectional"))
    )
    (net (code "76") (name "unconnected-(U$19-PadCHA+)") (class "Default")
      (node (ref "U$19") (pin "CHA+") (pinfunction "CHA+_CHA+") (pintype "bidirectional"))
    )
    (net (code "77") (name "unconnected-(U$19-PadCHB+)") (class "Default")
      (node (ref "U$19") (pin "CHB+") (pinfunction "CHB+_CHB+") (pintype "bidirectional"))
    )
    (net (code "78") (name "unconnected-(U$19-PadD1)") (class "Default")
      (node (ref "U$19") (pin "D1") (pinfunction "D1_D1") (pintype "bidirectional"))
    )
    (net (code "79") (name "unconnected-(U$19-PadD2)") (class "Default")
      (node (ref "U$19") (pin "D2") (pinfunction "D2_D2") (pintype "bidirectional"))
    )
    (net (code "80") (name "unconnected-(U$20-PadNC)") (class "Default")
      (node (ref "U$20") (pin "NC") (pinfunction "NC_NC") (pintype "bidirectional"))
    )
    (net (code "81") (name "unconnected-(U$20-PadVTR1)") (class "Default")
      (node (ref "U$20") (pin "VTR1") (pinfunction "VTR1_VTR1") (pintype "bidirectional"))
    )
    (net (code "82") (name "unconnected-(U$20-PadVTR8)") (class "Default")
      (node (ref "U$20") (pin "VTR8") (pinfunction "VTR8_VTR8") (pintype "bidirectional"))
    )
    (net (code "83") (name "unconnected-(U$25-PadX3)") (class "Default")
      (node (ref "U$25") (pin "X3") (pinfunction "X3_X3") (pintype "bidirectional"))
    )
  )
)
